# Mikrocontroller.net
KiCad netlist of a schematic drawn in Altium Designer
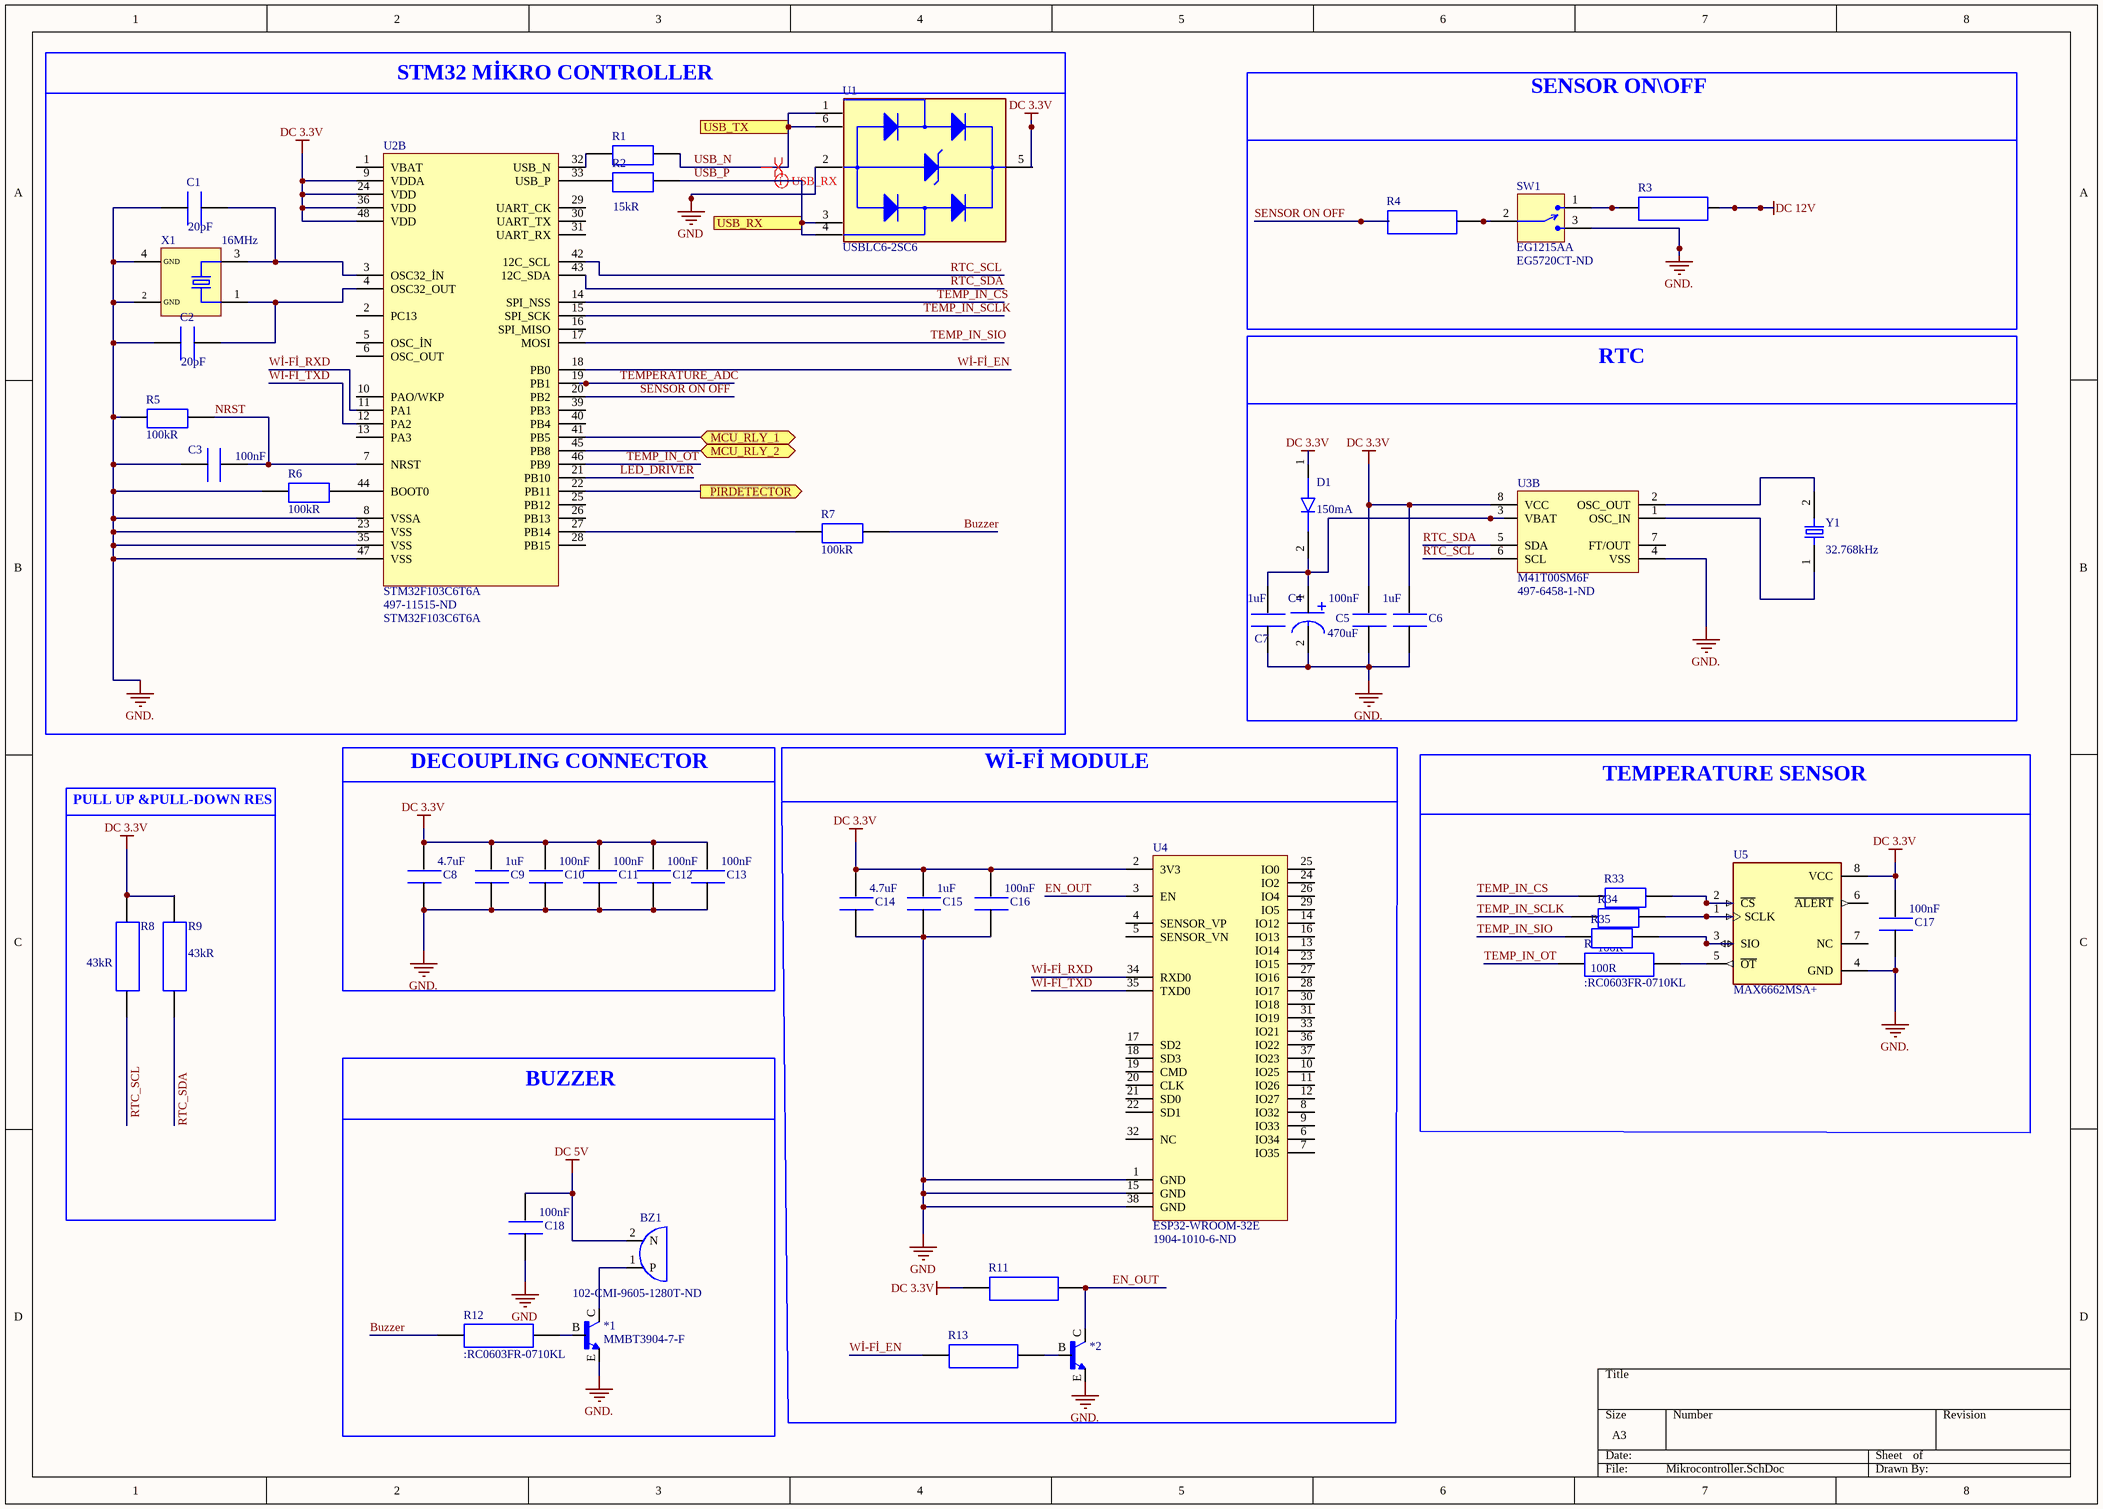
[diagram p0: Mikrocontroller.SchDoc]

(export (version "E")
  (design (tool "Eeschema 10.0.6"))
  (components
    (comp (ref "*1")
      (value "MMBT3904-7-F")
      (footprint "SOT23_F")
      (description "Transistor General Purpose BJT NPN 40 Volt 0.2A Automotive 3-Pin SOT-23")
      (fields (field (name "MANUFACTURER") "Diodes Zetex"))
      (libsource (lib "ALTİUM_PROJE.Integrated_Library1") (part "TRANS NPN 40V 0.2A SMD SOT23-3"))
    )
    (comp (ref "*2")
      (value "MMBT3904-7-F")
      (footprint "SOT23_F")
      (description "Transistor General Purpose BJT NPN 40 Volt 0.2A Automotive 3-Pin SOT-23")
      (fields (field (name "MANUFACTURER") "Diodes Zetex"))
      (libsource (lib "ALTİUM_PROJE.Integrated_Library1") (part "TRANS NPN 40V 0.2A SMD SOT23-3"))
    )
    (comp (ref "BZ1")
      (value "CMI-9605-1280T")
      (footprint "CMI-9605")
      (description "9.6 mm, 12 Vdc, 80 dB, Through Hole, Driving Circuit, Magnetic Audio Indicator Buzzer")
      (fields
        (field (name "MANUFACTURER") "CUI Devices")
        (field (name "SUPPLIER PART NUMBER 1") "102-CMI-9605-1280T-ND")
      )
      (libsource (lib "ALTİUM_PROJE.Integrated_Library1") (part "CMI-9605-1280T"))
    )
    (comp (ref "C1")
      (value "CL10C200JB8NNNC")
      (footprint "CAP_0603")
      (description "Ceramic capacitor SMD-0603 20pF /50V NP0# J +-5%, SAMSUNG, RoHS")
      (fields
        (field (name "MANUFACTURER") "Samsung")
        (field (name "TOLERANCE") "5%")
        (field (name "CAPACITANCE") "20pF")
      )
      (libsource (lib "ALTİUM_PROJE.Integrated_Library1") (part "CAP CER 20pF 0603"))
    )
    (comp (ref "C2")
      (value "CL10C200JB8NNNC")
      (footprint "CAP_0603")
      (description "Ceramic capacitor SMD-0603 20pF /50V NP0# J +-5%, SAMSUNG, RoHS")
      (fields
        (field (name "MANUFACTURER") "Samsung")
        (field (name "TOLERANCE") "5%")
        (field (name "CAPACITANCE") "20pF")
      )
      (libsource (lib "ALTİUM_PROJE.Integrated_Library1") (part "CAP CER 20pF 0603"))
    )
    (comp (ref "C3")
      (value "C0603C104K5RACTU")
      (footprint "CAP_0603")
      (description "CAP CEP 100nF %10 0603 SMD")
      (fields
        (field (name "MANUFACTURER") "KEMET")
        (field (name "TOLERANCE") "10%")
        (field (name "CAPACITANCE") "100nF")
      )
      (libsource (lib "ALTİUM_PROJE.Integrated_Library1") (part "CAP CEP 100nF 0603"))
    )
    (comp (ref "C4")
      (value "ESH477M050AH4AA")
      (footprint "CAP_RADİAL_D10_P5")
      (description "Cap, 470UF, 50V, Alu Elec, Radial")
      (fields
        (field (name "MANUFACTURER") "KEMET")
        (field (name "TOLERANCE") "20%")
        (field (name "CAPACITANCE") "470uF")
      )
      (libsource (lib "ALTİUM_PROJE.Integrated_Library1") (part "Cap, 470UF, 50V,"))
    )
    (comp (ref "C5")
      (value "C0603C104K5RACTU")
      (footprint "CAP_0603")
      (description "CAP CEP 100nF %10 0603 SMD")
      (fields
        (field (name "MANUFACTURER") "KEMET")
        (field (name "TOLERANCE") "10%")
        (field (name "CAPACITANCE") "100nF")
      )
      (libsource (lib "ALTİUM_PROJE.Integrated_Library1") (part "CAP CEP 100nF 0603"))
    )
    (comp (ref "C6")
      (value "CL21B105KBFNNNE")
      (footprint "CAP 0805")
      (description "Ceramic capacitor SMD-0805      %10 1UF")
      (fields
        (field (name "MANUFACTURER") "Samsung")
        (field (name "TOLERANCE") "10%")
        (field (name "CAPACITANCE") "1uF")
      )
      (libsource (lib "ALTİUM_PROJE.Integrated_Library1") (part "CAP CER 1UF"))
    )
    (comp (ref "C7")
      (value "CL21B105KBFNNNE")
      (footprint "CAP 0805")
      (description "Ceramic capacitor SMD-0805      %10 1UF")
      (fields
        (field (name "MANUFACTURER") "Samsung")
        (field (name "TOLERANCE") "10%")
        (field (name "CAPACITANCE") "1uF")
      )
      (libsource (lib "ALTİUM_PROJE.Integrated_Library1") (part "CAP CER 1UF"))
    )
    (comp (ref "C8")
      (value "CL21A475KAQNNNE")
      (footprint "CAP 0805")
      (description "Cap Cer 4.7uF %10 0805")
      (fields
        (field (name "MANUFACTURER") "Samsung")
        (field (name "TOLERANCE") "10%")
        (field (name "CAPACITANCE") "4.7uF")
      )
      (libsource (lib "ALTİUM_PROJE.Integrated_Library1") (part "CAP CER_0805"))
    )
    (comp (ref "C9")
      (value "CL21B105KBFNNNE")
      (footprint "CAP 0805")
      (description "Ceramic capacitor SMD-0805      %10 1UF")
      (fields
        (field (name "MANUFACTURER") "Samsung")
        (field (name "TOLERANCE") "10%")
        (field (name "CAPACITANCE") "1uF")
      )
      (libsource (lib "ALTİUM_PROJE.Integrated_Library1") (part "CAP CER 1UF"))
    )
    (comp (ref "C10")
      (value "C0603C104K5RACTU")
      (footprint "CAP_0603")
      (description "CAP CEP 100nF %10 0603 SMD")
      (fields
        (field (name "MANUFACTURER") "KEMET")
        (field (name "TOLERANCE") "10%")
        (field (name "CAPACITANCE") "100nF")
      )
      (libsource (lib "ALTİUM_PROJE.Integrated_Library1") (part "CAP CEP 100nF 0603"))
    )
    (comp (ref "C11")
      (value "C0603C104K5RACTU")
      (footprint "CAP_0603")
      (description "CAP CEP 100nF %10 0603 SMD")
      (fields
        (field (name "MANUFACTURER") "KEMET")
        (field (name "TOLERANCE") "10%")
        (field (name "CAPACITANCE") "100nF")
      )
      (libsource (lib "ALTİUM_PROJE.Integrated_Library1") (part "CAP CEP 100nF 0603"))
    )
    (comp (ref "C12")
      (value "C0603C104K5RACTU")
      (footprint "CAP_0603")
      (description "CAP CEP 100nF %10 0603 SMD")
      (fields
        (field (name "MANUFACTURER") "KEMET")
        (field (name "TOLERANCE") "10%")
        (field (name "CAPACITANCE") "100nF")
      )
      (libsource (lib "ALTİUM_PROJE.Integrated_Library1") (part "CAP CEP 100nF 0603"))
    )
    (comp (ref "C13")
      (value "C0603C104K5RACTU")
      (footprint "CAP_0603")
      (description "CAP CEP 100nF %10 0603 SMD")
      (fields
        (field (name "MANUFACTURER") "KEMET")
        (field (name "TOLERANCE") "10%")
        (field (name "CAPACITANCE") "100nF")
      )
      (libsource (lib "ALTİUM_PROJE.Integrated_Library1") (part "CAP CEP 100nF 0603"))
    )
    (comp (ref "C14")
      (value "CL21A475KAQNNNE")
      (footprint "CAP 0805")
      (description "Cap Cer 4.7uF %10 0805")
      (fields
        (field (name "MANUFACTURER") "Samsung")
        (field (name "TOLERANCE") "10%")
        (field (name "CAPACITANCE") "4.7uF")
      )
      (libsource (lib "ALTİUM_PROJE.Integrated_Library1") (part "CAP CER_0805"))
    )
    (comp (ref "C15")
      (value "CL21B105KBFNNNE")
      (footprint "CAP 0805")
      (description "Ceramic capacitor SMD-0805      %10 1UF")
      (fields
        (field (name "MANUFACTURER") "Samsung")
        (field (name "TOLERANCE") "10%")
        (field (name "CAPACITANCE") "1uF")
      )
      (libsource (lib "ALTİUM_PROJE.Integrated_Library1") (part "CAP CER 1UF"))
    )
    (comp (ref "C16")
      (value "C0603C104K5RACTU")
      (footprint "CAP_0603")
      (description "CAP CEP 100nF %10 0603 SMD")
      (fields
        (field (name "MANUFACTURER") "KEMET")
        (field (name "TOLERANCE") "10%")
        (field (name "CAPACITANCE") "100nF")
      )
      (libsource (lib "ALTİUM_PROJE.Integrated_Library1") (part "CAP CEP 100nF 0603"))
    )
    (comp (ref "C17")
      (value "C0603C104K5RACTU")
      (footprint "CAP_0603")
      (description "CAP CEP 100nF %10 0603 SMD")
      (fields
        (field (name "MANUFACTURER") "KEMET")
        (field (name "TOLERANCE") "10%")
        (field (name "CAPACITANCE") "100nF")
      )
      (libsource (lib "ALTİUM_PROJE.Integrated_Library1") (part "CAP CEP 100nF 0603"))
    )
    (comp (ref "C18")
      (value "C0603C104K5RACTU")
      (footprint "CAP_0603")
      (description "CAP CEP 100nF %10 0603 SMD")
      (fields
        (field (name "MANUFACTURER") "KEMET")
        (field (name "TOLERANCE") "10%")
        (field (name "CAPACITANCE") "100nF")
      )
      (libsource (lib "ALTİUM_PROJE.Integrated_Library1") (part "CAP CEP 100nF 0603"))
    )
    (comp (ref "D1")
      (value "1N4148WS")
      (footprint "DİODE GEN")
      (description "Diode Small Signal Switching 100V 0.15A Automotive 2-Pin SOD-323F T/R")
      (fields
        (field (name "MANUFACTURER") "ON Semiconductor / Fairchild")
        (field (name "AVERAGE RECTIFIED CURRENT") "150mA")
      )
      (libsource (lib "ALTİUM_PROJE.Integrated_Library1") (part "DIODE GEN PURP 75V 150MA SOD323F"))
    )
    (comp (ref "R1")
      (value "RT0603FRE1315KL")
      (footprint "RES_0603")
      (description "High Precision-High Stability Chip Resistor Thin Film 0603 15kOhm 1% Paper T/R")
      (fields
        (field (name "MANUFACTURER") "Yageo")
        (field (name "TOLERANCE") "1%")
        (field (name "RESISTANCE") "15kR")
      )
      (libsource (lib "ALTİUM_PROJE.Integrated_Library1") (part "RES 15K OHM"))
    )
    (comp (ref "R2")
      (value "RT0603FRE1315KL")
      (footprint "RES_0603")
      (description "High Precision-High Stability Chip Resistor Thin Film 0603 15kOhm 1% Paper T/R")
      (fields
        (field (name "MANUFACTURER") "Yageo")
        (field (name "TOLERANCE") "1%")
        (field (name "RESISTANCE") "15kR")
      )
      (libsource (lib "ALTİUM_PROJE.Integrated_Library1") (part "RES 15K OHM"))
    )
    (comp (ref "R3")
      (value ":RC0603FR-0710KL")
      (footprint "RES_0603")
      (description "RES 10K %1 OHM 0603 SMD")
      (fields
        (field (name "MANUFACTURER") "Yageo")
        (field (name "MANUFACTURER PART NUMBER") "RC0603FR-0710KL")
      )
      (libsource (lib "ALTİUM_PROJE.Integrated_Library1") (part "RES 10K OHM 0603"))
    )
    (comp (ref "R4")
      (value ":RC0603FR-0710KL")
      (footprint "RES_0603")
      (description "RES 10K %1 OHM 0603 SMD")
      (fields
        (field (name "MANUFACTURER") "Yageo")
        (field (name "MANUFACTURER PART NUMBER") "RC0603FR-0710KL")
      )
      (libsource (lib "ALTİUM_PROJE.Integrated_Library1") (part "RES 10K OHM 0603"))
    )
    (comp (ref "R5")
      (value "RE0603FRE07100KL")
      (footprint "RES_0603")
      (description "Res Thick Film 0603 100K Ohm 1% 1/10W ±50ppm/°C Molded SMD Paper T/R")
      (fields
        (field (name "MANUFACTURER") "Yageo")
        (field (name "TOLERANCE") "1%")
        (field (name "RESISTANCE") "100kR")
      )
      (libsource (lib "ALTİUM_PROJE.Integrated_Library1") (part "RES 100K OHM"))
    )
    (comp (ref "R6")
      (value "RE0603FRE07100KL")
      (footprint "RES_0603")
      (description "Res Thick Film 0603 100K Ohm 1% 1/10W ±50ppm/°C Molded SMD Paper T/R")
      (fields
        (field (name "MANUFACTURER") "Yageo")
        (field (name "TOLERANCE") "1%")
        (field (name "RESISTANCE") "100kR")
      )
      (libsource (lib "ALTİUM_PROJE.Integrated_Library1") (part "RES 100K OHM"))
    )
    (comp (ref "R7")
      (value "RE0603FRE07100KL")
      (footprint "RES_0603")
      (description "Res Thick Film 0603 100K Ohm 1% 1/10W ±50ppm/°C Molded SMD Paper T/R")
      (fields
        (field (name "MANUFACTURER") "Yageo")
        (field (name "TOLERANCE") "1%")
        (field (name "RESISTANCE") "100kR")
      )
      (libsource (lib "ALTİUM_PROJE.Integrated_Library1") (part "RES 100K OHM"))
    )
    (comp (ref "R8")
      (value "RC0603JR-0743KL")
      (footprint "RES_0603")
      (description "Res Thick Film 0603 43K Ohm 5% 0.1W(1/10W) ±100ppm/°C Pad SMD T/R")
      (fields
        (field (name "MANUFACTURER") "Yageo")
        (field (name "TOLERANCE") "5%")
        (field (name "RESISTANCE") "43kR")
      )
      (libsource (lib "ALTİUM_PROJE.Integrated_Library1") (part "RES 43K OHM 5%  0603"))
    )
    (comp (ref "R9")
      (value "RC0603JR-0743KL")
      (footprint "RES_0603")
      (description "Res Thick Film 0603 43K Ohm 5% 0.1W(1/10W) ±100ppm/°C Pad SMD T/R")
      (fields
        (field (name "MANUFACTURER") "Yageo")
        (field (name "TOLERANCE") "5%")
        (field (name "RESISTANCE") "43kR")
      )
      (libsource (lib "ALTİUM_PROJE.Integrated_Library1") (part "RES 43K OHM 5%  0603"))
    )
    (comp (ref "R10")
      (value ":RC0603FR-0710KL")
      (footprint "RES_0603")
      (description "RES 10K %1 OHM 0603 SMD")
      (fields
        (field (name "MANUFACTURER") "Yageo")
        (field (name "MANUFACTURER PART NUMBER") "RC0603FR-0710KL")
      )
      (libsource (lib "ALTİUM_PROJE.Integrated_Library1") (part "RES 10K OHM 0603"))
    )
    (comp (ref "R11")
      (value ":RC0603FR-0710KL")
      (footprint "RES_0603")
      (description "RES 10K %1 OHM 0603 SMD")
      (fields
        (field (name "MANUFACTURER") "Yageo")
        (field (name "MANUFACTURER PART NUMBER") "RC0603FR-0710KL")
      )
      (libsource (lib "ALTİUM_PROJE.Integrated_Library1") (part "RES 10K OHM 0603"))
    )
    (comp (ref "R12")
      (value ":RC0603FR-0710KL")
      (footprint "RES_0603")
      (description "RES 10K %1 OHM 0603 SMD")
      (fields
        (field (name "MANUFACTURER") "Yageo")
        (field (name "MANUFACTURER PART NUMBER") "RC0603FR-0710KL")
      )
      (libsource (lib "ALTİUM_PROJE.Integrated_Library1") (part "RES 10K OHM 0603"))
    )
    (comp (ref "R13")
      (value ":RC0603FR-0710KL")
      (footprint "RES_0603")
      (description "RES 10K %1 OHM 0603 SMD")
      (fields
        (field (name "MANUFACTURER") "Yageo")
        (field (name "MANUFACTURER PART NUMBER") "RC0603FR-0710KL")
      )
      (libsource (lib "ALTİUM_PROJE.Integrated_Library1") (part "RES 10K OHM 0603"))
    )
    (comp (ref "R33")
      (value "AC0603FR-10100RL")
      (footprint "RES_0603")
      (description "Chip Resistor Automotive Grade Thick Film 0603 100Ohm 1% Paper T/R")
      (fields
        (field (name "MANUFACTURER") "Yageo")
        (field (name "TOLERANCE") "1%")
        (field (name "RESISTANCE") "100R")
      )
      (libsource (lib "ALTİUM_PROJE.Integrated_Library1") (part "RES 100 OHM"))
    )
    (comp (ref "R34")
      (value "AC0603FR-10100RL")
      (footprint "RES_0603")
      (description "Chip Resistor Automotive Grade Thick Film 0603 100Ohm 1% Paper T/R")
      (fields
        (field (name "MANUFACTURER") "Yageo")
        (field (name "TOLERANCE") "1%")
        (field (name "RESISTANCE") "100R")
      )
      (libsource (lib "ALTİUM_PROJE.Integrated_Library1") (part "RES 100 OHM"))
    )
    (comp (ref "R35")
      (value "AC0603FR-10100RL")
      (footprint "RES_0603")
      (description "Chip Resistor Automotive Grade Thick Film 0603 100Ohm 1% Paper T/R")
      (fields
        (field (name "MANUFACTURER") "Yageo")
        (field (name "TOLERANCE") "1%")
        (field (name "RESISTANCE") "100R")
      )
      (libsource (lib "ALTİUM_PROJE.Integrated_Library1") (part "RES 100 OHM"))
    )
    (comp (ref "SW1")
      (value "EG1215AA")
      (footprint "EG1215AA")
      (description "Slide Switch, SPDT, 0.025A, 24V, SMD")
      (fields
        (field (name "MANUFACTURER") "E-Switch")
        (field (name "TOLERANCE") "4.95%")
        (field (name "SUPPLIER PART NUMBER 1") "EG5720CT-ND")
      )
      (libsource (lib "ALTİUM_PROJE.Integrated_Library1") (part "EG1215AA"))
    )
    (comp (ref "U1")
      (value "USBLC6-2SC6")
      (footprint "USBLC")
      (description "USBLC6 Series 2 Line 6 V Uni / Bi-Directional ESD Protection - SOT-23-6")
      (fields (field (name "MANUFACTURER") "STMicroelectronics"))
      (libsource (lib "ALTİUM_PROJE.Integrated_Library1") (part "TVS DIODE 5.25VWM 17VC SOT23-6"))
    )
    (comp (ref "U2")
      (value "STM32F103C6T6A")
      (footprint "LQFP-48")
      (description "MCU 32-bit STM32F ARM Cortex M3 RISC 32KB Flash 2.5V/3.3V 48-Pin LQFP Tray")
      (fields
        (field (name "MANUFACTURER") "STMicroelectronics")
        (field (name "SUPPLIER PART NUMBER 1") "497-11515-ND")
        (field (name "SUPPLIER PART NUMBER 2") "STM32F103C6T6A")
      )
      (libsource (lib "ALTİUM_PROJE.Integrated_Library1") (part "STM32F103C6T6A"))
    )
    (comp (ref "U3")
      (value "M41T00SM6F")
      (footprint "SOIC8")
      (description "Real-time Clocks Clock/Calendar I2C, 2-Wire Serial 70uA @ 2.7V ~ 5.5V SOIC-8_150mil RoHS")
      (fields
        (field (name "MANUFACTURER") "STMicroelectronics")
        (field (name "SUPPLIER PART NUMBER 1") "497-6458-1-ND")
      )
      (libsource (lib "ALTİUM_PROJE.Integrated_Library1") (part "M41T00SM6F"))
    )
    (comp (ref "U4")
      (value "ESP32-WROOM-32E")
      (footprint "ESP-32")
      (description "Bluetooth and Wi-Fi Module 2.4GHz to 2.5GHz 2.7V to 3.6V 38-Pin SMD Module")
      (fields
        (field (name "MANUFACTURER") "Espressif Systems")
        (field (name "MANUFACTURER PART NUMBER") "ESP32-WROOM-32E(4MB)")
        (field (name "SUPPLIER PART NUMBER 2") "1904-1010-6-ND")
      )
      (libsource (lib "ALTİUM_PROJE.Integrated_Library1") (part "ESP32-WROOM-32"))
    )
    (comp (ref "U5")
      (value "MAX6662MSA+")
      (footprint "SOIC127P600X175-8N")
      (description "Temp Sensor Digital Serial (3-Wire, SPI) 8-Pin SOIC N Tube")
      (fields (field (name "MANUFACTURER") "Maxim"))
      (libsource (lib "ALTİUM_PROJE.Integrated_Library1") (part "MAX6662MSA+"))
    )
    (comp (ref "X1")
      (value "ECS-160-20-30B-TR")
      (footprint "ECS")
      (description "Crystal 16MHz ±30ppm (Tol) ±50ppm (Stability) 20pF FUND 50Ohm 4-Pin Mini-SMD T/R")
      (fields
        (field (name "MANUFACTURER") "ECS International")
        (field (name "TOLERANCE") "50ppm")
        (field (name "FREQUENCY") "16MHz")
      )
      (libsource (lib "ALTİUM_PROJE.Integrated_Library1") (part "CRYSTAL 16MHz"))
    )
    (comp (ref "Y1")
      (value "ABS05-32.768KHZ-T")
      (footprint "Crystal 2-SMD")
      (description "ABRACON - ABS05-32.768KHZ-T - Crystal, 32.768 kHz, SMD, 1.6mm x 1mm, 12.5 pF, 20 ppm, ABS05 Series")
      (fields
        (field (name "MANUFACTURER") "Abracon")
        (field (name "TOLERANCE") "20ppm")
        (field (name "FREQUENCY") "32.768kHz")
      )
      (libsource (lib "ALTİUM_PROJE.Integrated_Library1") (part "CRYSTAL 32.7680KHZ 12.5PF SMD"))
    )
  )
  (nets
    (net (code "1") (name "/Buzzer") (class "Default")
      (node (ref "R12") (pin "1") (pinfunction "24_1") (pintype "passive"))
      (node (ref "R7") (pin "2") (pinfunction "25_2") (pintype "passive"))
    )
    (net (code "2") (name "/EN_OUT") (class "Default")
      (node (ref "*2") (pin "C") (pinfunction "C_C") (pintype "passive"))
      (node (ref "R11") (pin "2") (pinfunction "25_2") (pintype "passive"))
      (node (ref "U4") (pin "3") (pinfunction "EN_3") (pintype "passive"))
    )
    (net (code "3") (name "/LED_DRİVER") (class "Default")
      (node (ref "U2") (pin "21") (pinfunction "PB10_21") (pintype "passive"))
    )
    (net (code "4") (name "/MCU_RLY_1") (class "Default")
      (node (ref "U2") (pin "41") (pinfunction "PB5_41") (pintype "passive"))
    )
    (net (code "5") (name "/MCU_RLY_2") (class "Default")
      (node (ref "U2") (pin "45") (pinfunction "PB8_45") (pintype "passive"))
    )
    (net (code "6") (name "/NRST") (class "Default")
      (node (ref "C3") (pin "2") (pinfunction "29_2") (pintype "passive"))
      (node (ref "R5") (pin "2") (pinfunction "25_2") (pintype "passive"))
      (node (ref "U2") (pin "7") (pinfunction "NRST_7") (pintype "passive"))
    )
    (net (code "7") (name "/PIRDETECTOR") (class "Default")
      (node (ref "U2") (pin "22") (pinfunction "PB11_22") (pintype "passive"))
    )
    (net (code "8") (name "/RTC_SCL") (class "Default")
      (node (ref "R8") (pin "1") (pinfunction "24_1") (pintype "passive"))
      (node (ref "U2") (pin "42") (pinfunction "12C_SCL_42") (pintype "passive"))
      (node (ref "U3") (pin "6") (pinfunction "SCL_6") (pintype "passive"))
    )
    (net (code "9") (name "/RTC_SDA") (class "Default")
      (node (ref "R9") (pin "1") (pinfunction "24_1") (pintype "passive"))
      (node (ref "U2") (pin "43") (pinfunction "12C_SDA_43") (pintype "passive"))
      (node (ref "U3") (pin "5") (pinfunction "SDA_5") (pintype "passive"))
    )
    (net (code "10") (name "/SENSOR ON OFF") (class "Default")
      (node (ref "R4") (pin "1") (pinfunction "24_1") (pintype "passive"))
      (node (ref "U2") (pin "20") (pinfunction "PB2_20") (pintype "passive"))
    )
    (net (code "11") (name "/TEMPERATURE_ADC") (class "Default")
      (node (ref "U2") (pin "19") (pinfunction "PB1_19") (pintype "passive"))
    )
    (net (code "12") (name "/TEMP_IN_CS") (class "Default")
      (node (ref "R33") (pin "1") (pinfunction "24_1") (pintype "passive"))
      (node (ref "U2") (pin "14") (pinfunction "SPI_NSS_14") (pintype "passive"))
    )
    (net (code "13") (name "/TEMP_IN_OT") (class "Default")
      (node (ref "R10") (pin "1") (pinfunction "24_1") (pintype "passive"))
      (node (ref "U2") (pin "46") (pinfunction "PB9_46") (pintype "passive"))
    )
    (net (code "14") (name "/TEMP_IN_SCLK") (class "Default")
      (node (ref "R34") (pin "1") (pinfunction "24_1") (pintype "passive"))
      (node (ref "U2") (pin "15") (pinfunction "SPI_SCK_15") (pintype "passive"))
    )
    (net (code "15") (name "/TEMP_IN_SIO") (class "Default")
      (node (ref "R35") (pin "1") (pinfunction "24_1") (pintype "passive"))
      (node (ref "U2") (pin "17") (pinfunction "MOSI_17") (pintype "passive"))
    )
    (net (code "16") (name "/USB_N") (class "Default")
      (node (ref "R1") (pin "2") (pinfunction "25_2") (pintype "passive"))
      (node (ref "U1") (pin "1") (pinfunction "I/O1_1") (pintype "power_in"))
      (node (ref "U1") (pin "6") (pinfunction "I/O1_6") (pintype "power_in"))
    )
    (net (code "17") (name "/USB_P") (class "Default")
      (node (ref "R2") (pin "2") (pinfunction "25_2") (pintype "passive"))
      (node (ref "U1") (pin "3") (pinfunction "I/O2_3") (pintype "power_in"))
      (node (ref "U1") (pin "4") (pinfunction "I/O2_4") (pintype "power_in"))
    )
    (net (code "18") (name "/Wİ-Fİ_EN") (class "Default")
      (node (ref "R13") (pin "1") (pinfunction "24_1") (pintype "passive"))
      (node (ref "U2") (pin "18") (pinfunction "PB0_18") (pintype "passive"))
    )
    (net (code "19") (name "/Wİ-Fİ_RXD") (class "Default")
      (node (ref "U2") (pin "11") (pinfunction "PA1_11") (pintype "passive"))
      (node (ref "U4") (pin "34") (pinfunction "RXD0_34") (pintype "passive"))
    )
    (net (code "20") (name "/Wİ-Fİ_TXD") (class "Default")
      (node (ref "U2") (pin "12") (pinfunction "PA2_12") (pintype "passive"))
      (node (ref "U4") (pin "35") (pinfunction "TXD0_35") (pintype "passive"))
    )
    (net (code "21") (name "DC 3.3V") (class "Default")
      (node (ref "C10") (pin "2") (pinfunction "29_2") (pintype "passive"))
      (node (ref "C11") (pin "2") (pinfunction "29_2") (pintype "passive"))
      (node (ref "C12") (pin "2") (pinfunction "29_2") (pintype "passive"))
      (node (ref "C13") (pin "2") (pinfunction "29_2") (pintype "passive"))
      (node (ref "C14") (pin "2") (pinfunction "29_2") (pintype "passive"))
      (node (ref "C15") (pin "2") (pinfunction "29_2") (pintype "passive"))
      (node (ref "C16") (pin "2") (pinfunction "29_2") (pintype "passive"))
      (node (ref "C17") (pin "2") (pinfunction "29_2") (pintype "passive"))
      (node (ref "C5") (pin "2") (pinfunction "29_2") (pintype "passive"))
      (node (ref "C6") (pin "2") (pinfunction "29_2") (pintype "passive"))
      (node (ref "C8") (pin "2") (pinfunction "29_2") (pintype "passive"))
      (node (ref "C9") (pin "2") (pinfunction "29_2") (pintype "passive"))
      (node (ref "D1") (pin "1") (pinfunction "ANOT_1") (pintype "passive"))
      (node (ref "R11") (pin "1") (pinfunction "24_1") (pintype "passive"))
      (node (ref "R8") (pin "2") (pinfunction "25_2") (pintype "passive"))
      (node (ref "U2") (pin "24") (pinfunction "VDD_24") (pintype "passive"))
      (node (ref "U2") (pin "36") (pinfunction "VDD_36") (pintype "passive"))
      (node (ref "U2") (pin "48") (pinfunction "VDD_48") (pintype "passive"))
      (node (ref "U2") (pin "9") (pinfunction "VDDA_9") (pintype "passive"))
      (node (ref "U3") (pin "8") (pinfunction "VCC_8") (pintype "passive"))
      (node (ref "U4") (pin "2") (pinfunction "3V3_2") (pintype "passive"))
      (node (ref "U5") (pin "8") (pinfunction "VCC_8") (pintype "power_in"))
    )
    (net (code "22") (name "DC 5V") (class "Default")
      (node (ref "BZ1") (pin "2") (pinfunction "N_2") (pintype "passive"))
      (node (ref "C18") (pin "2") (pinfunction "29_2") (pintype "passive"))
    )
    (net (code "23") (name "DC 12V") (class "Default")
      (node (ref "R3") (pin "2") (pinfunction "25_2") (pintype "passive"))
    )
    (net (code "24") (name "GND") (class "Default")
      (node (ref "C14") (pin "1") (pinfunction "28_1") (pintype "passive"))
      (node (ref "C15") (pin "1") (pinfunction "28_1") (pintype "passive"))
      (node (ref "C16") (pin "1") (pinfunction "28_1") (pintype "passive"))
      (node (ref "C18") (pin "1") (pinfunction "28_1") (pintype "passive"))
      (node (ref "U1") (pin "2") (pinfunction "GND_2") (pintype "power_in"))
      (node (ref "U4") (pin "1") (pinfunction "GND_1") (pintype "passive"))
      (node (ref "U4") (pin "15") (pinfunction "GND_15") (pintype "passive"))
      (node (ref "U4") (pin "38") (pinfunction "GND_38") (pintype "passive"))
    )
    (net (code "25") (name "GND.") (class "Default")
      (node (ref "*1") (pin "E") (pinfunction "E_E") (pintype "passive"))
      (node (ref "*2") (pin "E") (pinfunction "E_E") (pintype "passive"))
      (node (ref "C1") (pin "1") (pinfunction "28_1") (pintype "passive"))
      (node (ref "C10") (pin "1") (pinfunction "28_1") (pintype "passive"))
      (node (ref "C11") (pin "1") (pinfunction "28_1") (pintype "passive"))
      (node (ref "C12") (pin "1") (pinfunction "28_1") (pintype "passive"))
      (node (ref "C13") (pin "1") (pinfunction "28_1") (pintype "passive"))
      (node (ref "C17") (pin "1") (pinfunction "28_1") (pintype "passive"))
      (node (ref "C2") (pin "1") (pinfunction "28_1") (pintype "passive"))
      (node (ref "C3") (pin "1") (pinfunction "28_1") (pintype "passive"))
      (node (ref "C4") (pin "2") (pinfunction "1_2") (pintype "passive"))
      (node (ref "C5") (pin "1") (pinfunction "28_1") (pintype "passive"))
      (node (ref "C6") (pin "1") (pinfunction "28_1") (pintype "passive"))
      (node (ref "C7") (pin "1") (pinfunction "28_1") (pintype "passive"))
      (node (ref "C8") (pin "1") (pinfunction "28_1") (pintype "passive"))
      (node (ref "C9") (pin "1") (pinfunction "28_1") (pintype "passive"))
      (node (ref "R5") (pin "1") (pinfunction "24_1") (pintype "passive"))
      (node (ref "R6") (pin "1") (pinfunction "24_1") (pintype "passive"))
      (node (ref "U2") (pin "23") (pinfunction "VSS_23") (pintype "passive"))
      (node (ref "U2") (pin "35") (pinfunction "VSS_35") (pintype "passive"))
      (node (ref "U2") (pin "47") (pinfunction "VSS_47") (pintype "passive"))
      (node (ref "U2") (pin "8") (pinfunction "VSSA_8") (pintype "passive"))
      (node (ref "U3") (pin "4") (pinfunction "VSS_4") (pintype "passive"))
      (node (ref "U5") (pin "4") (pinfunction "GND_4") (pintype "power_in"))
      (node (ref "X1") (pin "2") (pinfunction "GND_2") (pintype "passive"))
      (node (ref "X1") (pin "4") (pinfunction "GND_4") (pintype "passive"))
    )
    (net (code "26") (name "Net-(BZ1-P)") (class "Default")
      (node (ref "*1") (pin "C") (pinfunction "C_C") (pintype "passive"))
      (node (ref "BZ1") (pin "1") (pinfunction "P_1") (pintype "passive"))
    )
    (net (code "27") (name "Net-(C1-29)") (class "Default")
      (node (ref "C1") (pin "2") (pinfunction "29_2") (pintype "passive"))
      (node (ref "U2") (pin "3") (pinfunction "OSC32_İN_3") (pintype "passive"))
      (node (ref "X1") (pin "3") (pinfunction "2_3") (pintype "passive"))
    )
    (net (code "28") (name "Net-(C2-29)") (class "Default")
      (node (ref "C2") (pin "2") (pinfunction "29_2") (pintype "passive"))
      (node (ref "U2") (pin "4") (pinfunction "OSC32_OUT_4") (pintype "passive"))
      (node (ref "X1") (pin "1") (pinfunction "1_1") (pintype "passive"))
    )
    (net (code "29") (name "Net-(C7-29)") (class "Default")
      (node (ref "C4") (pin "1") (pintype "passive"))
      (node (ref "C7") (pin "2") (pinfunction "29_2") (pintype "passive"))
      (node (ref "D1") (pin "2") (pinfunction "CAOTHODE_2") (pintype "passive"))
      (node (ref "U3") (pin "3") (pinfunction "VBAT_3") (pintype "passive"))
    )
    (net (code "30") (name "Net-(R1-24)") (class "Default")
      (node (ref "R1") (pin "1") (pinfunction "24_1") (pintype "passive"))
      (node (ref "U2") (pin "32") (pinfunction "USB_N_32") (pintype "passive"))
    )
    (net (code "31") (name "Net-(R2-24)") (class "Default")
      (node (ref "R2") (pin "1") (pinfunction "24_1") (pintype "passive"))
      (node (ref "U2") (pin "33") (pinfunction "USB_P_33") (pintype "passive"))
    )
    (net (code "32") (name "Net-(R6-25)") (class "Default")
      (node (ref "R6") (pin "2") (pinfunction "25_2") (pintype "passive"))
      (node (ref "U2") (pin "44") (pinfunction "BOOT0_44") (pintype "passive"))
    )
    (net (code "33") (name "Net-(R7-24)") (class "Default")
      (node (ref "R7") (pin "1") (pinfunction "24_1") (pintype "passive"))
      (node (ref "U2") (pin "27") (pinfunction "PB14_27") (pintype "passive"))
    )
    (net (code "34") (name "Net-(R10-25)") (class "Default")
      (node (ref "R10") (pin "2") (pinfunction "25_2") (pintype "passive"))
      (node (ref "U5") (pin "5") (pinfunction "~{OT}_5") (pintype "output"))
    )
    (net (code "35") (name "Net-(R12-25)") (class "Default")
      (node (ref "*1") (pin "B") (pinfunction "B_B") (pintype "passive"))
      (node (ref "R12") (pin "2") (pinfunction "25_2") (pintype "passive"))
    )
    (net (code "36") (name "Net-(R13-25)") (class "Default")
      (node (ref "*2") (pin "B") (pinfunction "B_B") (pintype "passive"))
      (node (ref "R13") (pin "2") (pinfunction "25_2") (pintype "passive"))
    )
    (net (code "37") (name "Net-(R33-25)") (class "Default")
      (node (ref "R33") (pin "2") (pinfunction "25_2") (pintype "passive"))
      (node (ref "U5") (pin "2") (pinfunction "~{CS}_2") (pintype "input"))
    )
    (net (code "38") (name "Net-(R34-25)") (class "Default")
      (node (ref "R34") (pin "2") (pinfunction "25_2") (pintype "passive"))
      (node (ref "U5") (pin "1") (pinfunction "SCLK_1") (pintype "input"))
    )
    (net (code "39") (name "Net-(R35-25)") (class "Default")
      (node (ref "R35") (pin "2") (pinfunction "25_2") (pintype "passive"))
      (node (ref "U5") (pin "3") (pinfunction "SIO_3") (pintype "bidirectional"))
    )
    (net (code "40") (name "Net-(U3B-OSC_IN)") (class "Default")
      (node (ref "U3") (pin "1") (pinfunction "OSC_IN_1") (pintype "passive"))
      (node (ref "Y1") (pin "1") (pinfunction "1_1") (pintype "passive"))
    )
    (net (code "41") (name "Net-(U3B-OSC_OUT)") (class "Default")
      (node (ref "U3") (pin "2") (pinfunction "OSC_OUT_2") (pintype "passive"))
      (node (ref "Y1") (pin "2") (pinfunction "2_2") (pintype "passive"))
    )
    (net (code "42") (name "unconnected-(R3-24-Pad1)") (class "Default")
      (node (ref "R3") (pin "1") (pinfunction "24_1") (pintype "passive"))
    )
    (net (code "43") (name "unconnected-(R4-25-Pad2)") (class "Default")
      (node (ref "R4") (pin "2") (pinfunction "25_2") (pintype "passive"))
    )
    (net (code "44") (name "unconnected-(R9-25-Pad2)") (class "Default")
      (node (ref "R9") (pin "2") (pinfunction "25_2") (pintype "passive"))
    )
    (net (code "45") (name "unconnected-(SW1-Pad1)") (class "Default")
      (node (ref "SW1") (pin "1") (pintype "passive"))
    )
    (net (code "46") (name "unconnected-(SW1-Pad2)") (class "Default")
      (node (ref "SW1") (pin "2") (pintype "passive"))
    )
    (net (code "47") (name "unconnected-(SW1-Pad3)") (class "Default")
      (node (ref "SW1") (pin "3") (pintype "passive"))
    )
    (net (code "48") (name "unconnected-(U1-VBUS-Pad5)") (class "Default")
      (node (ref "U1") (pin "5") (pinfunction "VBUS_5") (pintype "power_in"))
    )
    (net (code "49") (name "unconnected-(U2B-OSC_OUT-Pad6)") (class "Default")
      (node (ref "U2") (pin "6") (pinfunction "OSC_OUT_6") (pintype "passive"))
    )
    (net (code "50") (name "unconnected-(U2B-OSC_İN-Pad5)") (class "Default")
      (node (ref "U2") (pin "5") (pinfunction "OSC_İN_5") (pintype "passive"))
    )
    (net (code "51") (name "unconnected-(U2B-PA3-Pad13)") (class "Default")
      (node (ref "U2") (pin "13") (pinfunction "PA3_13") (pintype "passive"))
    )
    (net (code "52") (name "unconnected-(U2B-PAO{slash}WKP-Pad10)") (class "Default")
      (node (ref "U2") (pin "10") (pinfunction "PAO/WKP_10") (pintype "passive"))
    )
    (net (code "53") (name "unconnected-(U2B-PB3-Pad39)") (class "Default")
      (node (ref "U2") (pin "39") (pinfunction "PB3_39") (pintype "passive"))
    )
    (net (code "54") (name "unconnected-(U2B-PB4-Pad40)") (class "Default")
      (node (ref "U2") (pin "40") (pinfunction "PB4_40") (pintype "passive"))
    )
    (net (code "55") (name "unconnected-(U2B-PB12-Pad25)") (class "Default")
      (node (ref "U2") (pin "25") (pinfunction "PB12_25") (pintype "passive"))
    )
    (net (code "56") (name "unconnected-(U2B-PB13-Pad26)") (class "Default")
      (node (ref "U2") (pin "26") (pinfunction "PB13_26") (pintype "passive"))
    )
    (net (code "57") (name "unconnected-(U2B-PB15-Pad28)") (class "Default")
      (node (ref "U2") (pin "28") (pinfunction "PB15_28") (pintype "passive"))
    )
    (net (code "58") (name "unconnected-(U2B-PC13-Pad2)") (class "Default")
      (node (ref "U2") (pin "2") (pinfunction "PC13_2") (pintype "passive"))
    )
    (net (code "59") (name "unconnected-(U2B-SPI_MISO-Pad16)") (class "Default")
      (node (ref "U2") (pin "16") (pinfunction "SPI_MISO_16") (pintype "passive"))
    )
    (net (code "60") (name "unconnected-(U2B-UART_CK-Pad29)") (class "Default")
      (node (ref "U2") (pin "29") (pinfunction "UART_CK_29") (pintype "passive"))
    )
    (net (code "61") (name "unconnected-(U2B-UART_RX-Pad31)") (class "Default")
      (node (ref "U2") (pin "31") (pinfunction "UART_RX_31") (pintype "passive"))
    )
    (net (code "62") (name "unconnected-(U2B-UART_TX-Pad30)") (class "Default")
      (node (ref "U2") (pin "30") (pinfunction "UART_TX_30") (pintype "passive"))
    )
    (net (code "63") (name "unconnected-(U2B-VBAT-Pad1)") (class "Default")
      (node (ref "U2") (pin "1") (pinfunction "VBAT_1") (pintype "passive"))
    )
    (net (code "64") (name "unconnected-(U3B-FT{slash}OUT-Pad7)") (class "Default")
      (node (ref "U3") (pin "7") (pinfunction "FT/OUT_7") (pintype "passive"))
    )
    (net (code "65") (name "unconnected-(U4-CLK-Pad20)") (class "Default")
      (node (ref "U4") (pin "20") (pinfunction "CLK_20") (pintype "passive"))
    )
    (net (code "66") (name "unconnected-(U4-CMD-Pad19)") (class "Default")
      (node (ref "U4") (pin "19") (pinfunction "CMD_19") (pintype "passive"))
    )
    (net (code "67") (name "unconnected-(U4-IO0-Pad25)") (class "Default")
      (node (ref "U4") (pin "25") (pinfunction "IO0_25") (pintype "passive"))
    )
    (net (code "68") (name "unconnected-(U4-IO2-Pad24)") (class "Default")
      (node (ref "U4") (pin "24") (pinfunction "IO2_24") (pintype "passive"))
    )
    (net (code "69") (name "unconnected-(U4-IO4-Pad26)") (class "Default")
      (node (ref "U4") (pin "26") (pinfunction "IO4_26") (pintype "passive"))
    )
    (net (code "70") (name "unconnected-(U4-IO5-Pad29)") (class "Default")
      (node (ref "U4") (pin "29") (pinfunction "IO5_29") (pintype "passive"))
    )
    (net (code "71") (name "unconnected-(U4-IO12-Pad14)") (class "Default")
      (node (ref "U4") (pin "14") (pinfunction "IO12_14") (pintype "passive"))
    )
    (net (code "72") (name "unconnected-(U4-IO13-Pad16)") (class "Default")
      (node (ref "U4") (pin "16") (pinfunction "IO13_16") (pintype "passive"))
    )
    (net (code "73") (name "unconnected-(U4-IO14-Pad13)") (class "Default")
      (node (ref "U4") (pin "13") (pinfunction "IO14_13") (pintype "passive"))
    )
    (net (code "74") (name "unconnected-(U4-IO15-Pad23)") (class "Default")
      (node (ref "U4") (pin "23") (pinfunction "IO15_23") (pintype "passive"))
    )
    (net (code "75") (name "unconnected-(U4-IO16-Pad27)") (class "Default")
      (node (ref "U4") (pin "27") (pinfunction "IO16_27") (pintype "passive"))
    )
    (net (code "76") (name "unconnected-(U4-IO17-Pad28)") (class "Default")
      (node (ref "U4") (pin "28") (pinfunction "IO17_28") (pintype "passive"))
    )
    (net (code "77") (name "unconnected-(U4-IO18-Pad30)") (class "Default")
      (node (ref "U4") (pin "30") (pinfunction "IO18_30") (pintype "passive"))
    )
    (net (code "78") (name "unconnected-(U4-IO19-Pad31)") (class "Default")
      (node (ref "U4") (pin "31") (pinfunction "IO19_31") (pintype "passive"))
    )
    (net (code "79") (name "unconnected-(U4-IO21-Pad33)") (class "Default")
      (node (ref "U4") (pin "33") (pinfunction "IO21_33") (pintype "passive"))
    )
    (net (code "80") (name "unconnected-(U4-IO22-Pad36)") (class "Default")
      (node (ref "U4") (pin "36") (pinfunction "IO22_36") (pintype "passive"))
    )
    (net (code "81") (name "unconnected-(U4-IO23-Pad37)") (class "Default")
      (node (ref "U4") (pin "37") (pinfunction "IO23_37") (pintype "passive"))
    )
    (net (code "82") (name "unconnected-(U4-IO25-Pad10)") (class "Default")
      (node (ref "U4") (pin "10") (pinfunction "IO25_10") (pintype "passive"))
    )
    (net (code "83") (name "unconnected-(U4-IO26-Pad11)") (class "Default")
      (node (ref "U4") (pin "11") (pinfunction "IO26_11") (pintype "passive"))
    )
    (net (code "84") (name "unconnected-(U4-IO27-Pad12)") (class "Default")
      (node (ref "U4") (pin "12") (pinfunction "IO27_12") (pintype "passive"))
    )
    (net (code "85") (name "unconnected-(U4-IO32-Pad8)") (class "Default")
      (node (ref "U4") (pin "8") (pinfunction "IO32_8") (pintype "passive"))
    )
    (net (code "86") (name "unconnected-(U4-IO33-Pad9)") (class "Default")
      (node (ref "U4") (pin "9") (pinfunction "IO33_9") (pintype "passive"))
    )
    (net (code "87") (name "unconnected-(U4-IO34-Pad6)") (class "Default")
      (node (ref "U4") (pin "6") (pinfunction "IO34_6") (pintype "passive"))
    )
    (net (code "88") (name "unconnected-(U4-IO35-Pad7)") (class "Default")
      (node (ref "U4") (pin "7") (pinfunction "IO35_7") (pintype "passive"))
    )
    (net (code "89") (name "unconnected-(U4-NC-Pad32)") (class "Default")
      (node (ref "U4") (pin "32") (pinfunction "NC_32") (pintype "passive"))
    )
    (net (code "90") (name "unconnected-(U4-SD0-Pad21)") (class "Default")
      (node (ref "U4") (pin "21") (pinfunction "SD0_21") (pintype "passive"))
    )
    (net (code "91") (name "unconnected-(U4-SD1-Pad22)") (class "Default")
      (node (ref "U4") (pin "22") (pinfunction "SD1_22") (pintype "passive"))
    )
    (net (code "92") (name "unconnected-(U4-SD2-Pad17)") (class "Default")
      (node (ref "U4") (pin "17") (pinfunction "SD2_17") (pintype "passive"))
    )
    (net (code "93") (name "unconnected-(U4-SD3-Pad18)") (class "Default")
      (node (ref "U4") (pin "18") (pinfunction "SD3_18") (pintype "passive"))
    )
    (net (code "94") (name "unconnected-(U4-SENSOR_VN-Pad5)") (class "Default")
      (node (ref "U4") (pin "5") (pinfunction "SENSOR_VN_5") (pintype "passive"))
    )
    (net (code "95") (name "unconnected-(U4-SENSOR_VP-Pad4)") (class "Default")
      (node (ref "U4") (pin "4") (pinfunction "SENSOR_VP_4") (pintype "passive"))
    )
    (net (code "96") (name "unconnected-(U5-NC-Pad7)") (class "Default")
      (node (ref "U5") (pin "7") (pinfunction "NC_7") (pintype "passive"))
    )
    (net (code "97") (name "unconnected-(U5-~{ALERT}-Pad6)") (class "Default")
      (node (ref "U5") (pin "6") (pinfunction "~{ALERT}_6") (pintype "output"))
    )
  )
)
